# Manan_Chugh.net
KiCad netlist of a schematic drawn in EAGLE
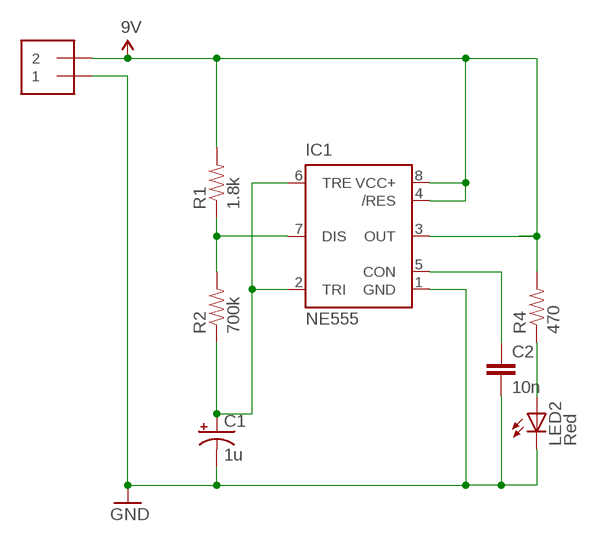
[diagram p0: schematic, sheet 1]

(export (version "E")
  (design (tool "Eeschema 10.0.6"))
  (components
    (comp (ref "C1")
      (value "1u")
      (footprint "eagle-import:CPOL-RADIAL-10UF-25V")
      (libsource (lib "eagle-import") (part "CAP_POLPTH2"))
    )
    (comp (ref "C2")
      (value "10n")
      (footprint "eagle-import:CAP-PTH-SMALL")
      (libsource (lib "eagle-import") (part "CAPPTH"))
    )
    (comp (ref "IC1")
      (value "NE555")
      (footprint "eagle-import:DIL-08")
      (fields (field (name "MF") "Arrow Electronics") (field (name "MPN") "NE555N"))
      (libsource (lib "eagle-import") (part "NE555"))
    )
    (comp (ref "J1")
      (value "1X2-3.5MM")
      (footprint "eagle-import:1X2-3.5MM")
      (libsource (lib "eagle-import") (part "1X2-3.5MM"))
    )
    (comp (ref "LED2")
      (value "Red")
      (footprint "eagle-import:LED5MM")
      (libsource (lib "eagle-import") (part "LED5MM"))
    )
    (comp (ref "R1")
      (value "1.8k")
      (footprint "eagle-import:AXIAL-0.3")
      (libsource (lib "eagle-import") (part "RESISTORAXIAL-0.3"))
    )
    (comp (ref "R2")
      (value "700k")
      (footprint "eagle-import:AXIAL-0.3")
      (libsource (lib "eagle-import") (part "RESISTORAXIAL-0.3"))
    )
    (comp (ref "R4")
      (value "470")
      (footprint "eagle-import:AXIAL-0.3")
      (libsource (lib "eagle-import") (part "RESISTORAXIAL-0.3"))
    )
  )
  (nets
    (net (code "1") (name "9V") (class "Default")
      (node (ref "IC1") (pin "3") (pinfunction "OUT_3") (pintype "output"))
      (node (ref "IC1") (pin "4") (pinfunction "/RES_4") (pintype "input"))
      (node (ref "IC1") (pin "8") (pinfunction "VCC+_8") (pintype "power_in"))
      (node (ref "J1") (pin "2") (pinfunction "2_2") (pintype "passive"))
      (node (ref "R1") (pin "P$2") (pinfunction "2_P$2") (pintype "passive"))
      (node (ref "R4") (pin "P$2") (pinfunction "2_P$2") (pintype "passive"))
    )
    (net (code "2") (name "GND") (class "Default")
      (node (ref "C1") (pin "2") (pinfunction "-_2") (pintype "passive"))
      (node (ref "C2") (pin "2") (pinfunction "2_2") (pintype "passive"))
      (node (ref "IC1") (pin "1") (pinfunction "GND_1") (pintype "power_in"))
      (node (ref "J1") (pin "1") (pinfunction "1_1") (pintype "passive"))
      (node (ref "LED2") (pin "K") (pinfunction "C_K") (pintype "passive"))
    )
    (net (code "3") (name "Net-(C1-+)") (class "Default")
      (node (ref "C1") (pin "1") (pinfunction "+_1") (pintype "passive"))
      (node (ref "IC1") (pin "2") (pinfunction "TRI_2") (pintype "input"))
      (node (ref "IC1") (pin "6") (pinfunction "TRE_6") (pintype "input"))
      (node (ref "R2") (pin "P$1") (pinfunction "1_P$1") (pintype "passive"))
    )
    (net (code "4") (name "Net-(IC1-CON)") (class "Default")
      (node (ref "C2") (pin "1") (pinfunction "1_1") (pintype "passive"))
      (node (ref "IC1") (pin "5") (pinfunction "CON_5") (pintype "input"))
    )
    (net (code "5") (name "Net-(IC1-DIS)") (class "Default")
      (node (ref "IC1") (pin "7") (pinfunction "DIS_7") (pintype "input"))
      (node (ref "R1") (pin "P$1") (pinfunction "1_P$1") (pintype "passive"))
      (node (ref "R2") (pin "P$2") (pinfunction "2_P$2") (pintype "passive"))
    )
    (net (code "6") (name "Net-(R4-1)") (class "Default")
      (node (ref "LED2") (pin "A") (pinfunction "A_A") (pintype "passive"))
      (node (ref "R4") (pin "P$1") (pinfunction "1_P$1") (pintype "passive"))
    )
  )
)
